# Display-Board_Rack-PDU_2_0.net
KiCad netlist of a schematic drawn in EAGLE
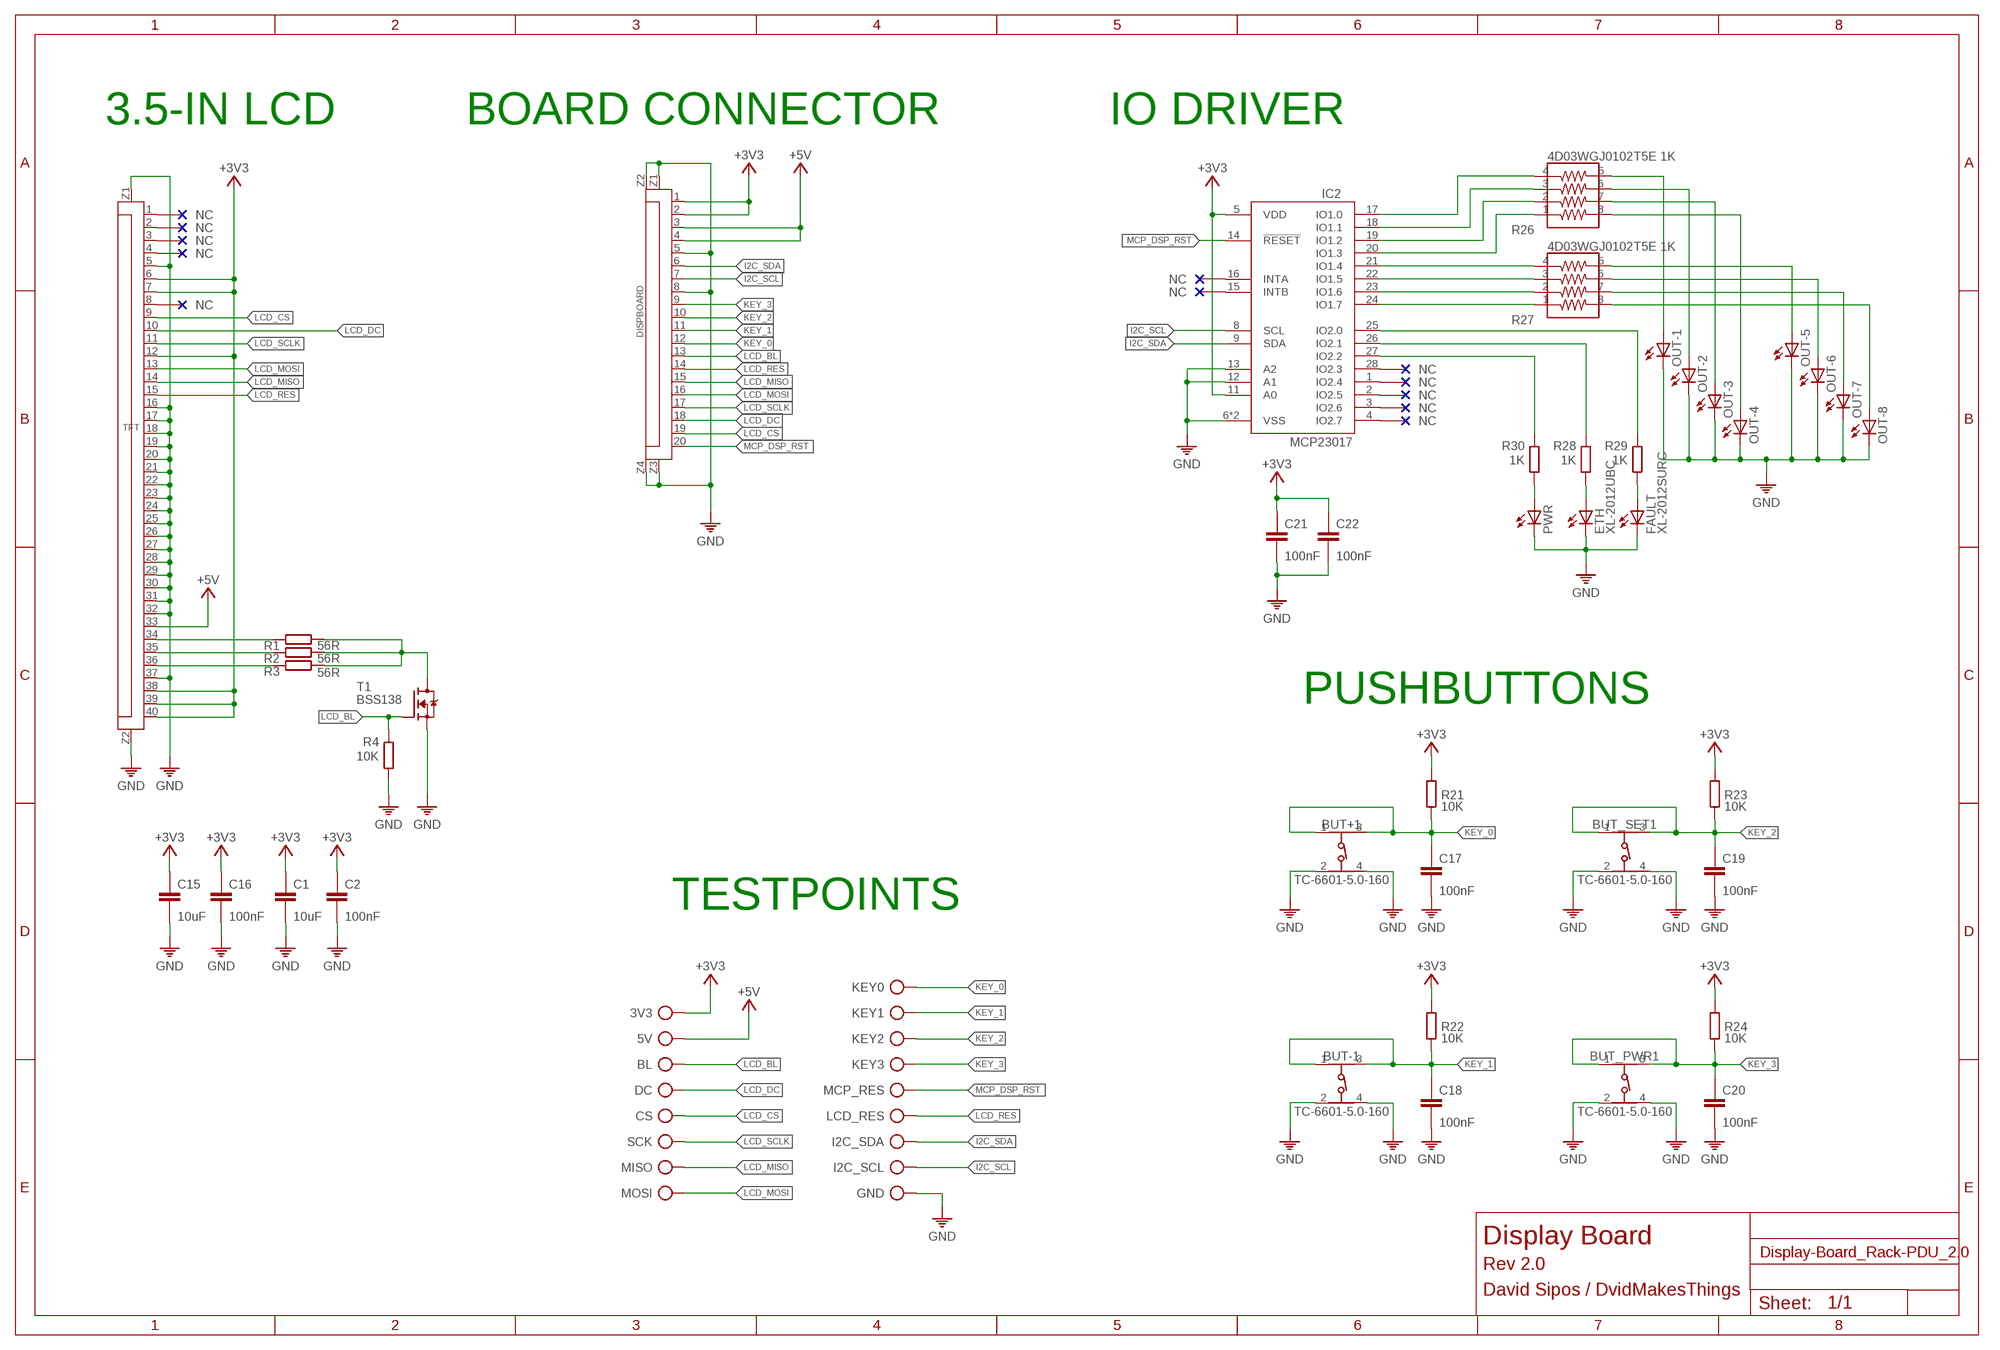
[diagram p0: schematic, sheet 1]

(export (version "E")
  (design (tool "Eeschema 10.0.6"))
  (components
    (comp (ref "3V3") (value "TP") (footprint "eagle-import:TP") (libsource (lib "eagle-import") (part "TP")))
    (comp (ref "5V") (value "TP") (footprint "eagle-import:TP") (libsource (lib "eagle-import") (part "TP")))
    (comp (ref "BL") (value "TP") (footprint "eagle-import:TP") (libsource (lib "eagle-import") (part "TP")))
    (comp (ref "BUT+1")
      (value "TC-6601-5.0-160")
      (footprint "eagle-import:430182043816")
      (libsource (lib "eagle-import") (part "430182043816"))
    )
    (comp (ref "BUT-1")
      (value "TC-6601-5.0-160")
      (footprint "eagle-import:430182043816")
      (libsource (lib "eagle-import") (part "430182043816"))
    )
    (comp (ref "BUT_PWR1")
      (value "TC-6601-5.0-160")
      (footprint "eagle-import:430182043816")
      (libsource (lib "eagle-import") (part "430182043816"))
    )
    (comp (ref "BUT_SET1")
      (value "TC-6601-5.0-160")
      (footprint "eagle-import:430182043816")
      (libsource (lib "eagle-import") (part "430182043816"))
    )
    (comp (ref "C1")
      (value "10uF")
      (footprint "eagle-import:C0402")
      (libsource (lib "eagle-import") (part "C-0402"))
    )
    (comp (ref "C2")
      (value "100nF")
      (footprint "eagle-import:C0402")
      (libsource (lib "eagle-import") (part "C-0402"))
    )
    (comp (ref "C15")
      (value "10uF")
      (footprint "eagle-import:C0402")
      (libsource (lib "eagle-import") (part "C-0402"))
    )
    (comp (ref "C16")
      (value "100nF")
      (footprint "eagle-import:C0402")
      (libsource (lib "eagle-import") (part "C-0402"))
    )
    (comp (ref "C17")
      (value "100nF")
      (footprint "eagle-import:C0402")
      (libsource (lib "eagle-import") (part "C-0402"))
    )
    (comp (ref "C18")
      (value "100nF")
      (footprint "eagle-import:C0402")
      (libsource (lib "eagle-import") (part "C-0402"))
    )
    (comp (ref "C19")
      (value "100nF")
      (footprint "eagle-import:C0402")
      (libsource (lib "eagle-import") (part "C-0402"))
    )
    (comp (ref "C20")
      (value "100nF")
      (footprint "eagle-import:C0402")
      (libsource (lib "eagle-import") (part "C-0402"))
    )
    (comp (ref "C21")
      (value "100nF")
      (footprint "eagle-import:C0402")
      (libsource (lib "eagle-import") (part "C-0402"))
    )
    (comp (ref "C22")
      (value "100nF")
      (footprint "eagle-import:C0402")
      (libsource (lib "eagle-import") (part "C-0402"))
    )
    (comp (ref "CS") (value "TP") (footprint "eagle-import:TP") (libsource (lib "eagle-import") (part "TP")))
    (comp (ref "DC") (value "TP") (footprint "eagle-import:TP") (libsource (lib "eagle-import") (part "TP")))
    (comp (ref "DISPBOARD")
      (value "FPC20-H")
      (footprint "eagle-import:FPC20")
      (libsource (lib "eagle-import") (part "FPC20-H"))
    )
    (comp (ref "ETH")
      (value "XL-2012UBC")
      (footprint "eagle-import:CHIP-LED0805")
      (libsource (lib "eagle-import") (part "LEDCHIP-LED0805"))
    )
    (comp (ref "FAULT")
      (value "XL-2012SURC")
      (footprint "eagle-import:CHIP-LED0805")
      (libsource (lib "eagle-import") (part "LEDCHIP-LED0805"))
    )
    (comp (ref "GND") (value "TP") (footprint "eagle-import:TP") (libsource (lib "eagle-import") (part "TP")))
    (comp (ref "I2C_SCL")
      (value "TP")
      (footprint "eagle-import:TP")
      (libsource (lib "eagle-import") (part "TP"))
    )
    (comp (ref "I2C_SDA")
      (value "TP")
      (footprint "eagle-import:TP")
      (libsource (lib "eagle-import") (part "TP"))
    )
    (comp (ref "IC2")
      (value "MCP23017-E/ML")
      (footprint "eagle-import:QFN28[6X6]ML")
      (libsource (lib "eagle-import") (part "MCP23017-E/ML"))
    )
    (comp (ref "KEY0")
      (value "TP")
      (footprint "eagle-import:TP")
      (libsource (lib "eagle-import") (part "TP"))
    )
    (comp (ref "KEY1")
      (value "TP")
      (footprint "eagle-import:TP")
      (libsource (lib "eagle-import") (part "TP"))
    )
    (comp (ref "KEY2")
      (value "TP")
      (footprint "eagle-import:TP")
      (libsource (lib "eagle-import") (part "TP"))
    )
    (comp (ref "KEY3")
      (value "TP")
      (footprint "eagle-import:TP")
      (libsource (lib "eagle-import") (part "TP"))
    )
    (comp (ref "LCD_RES")
      (value "TP")
      (footprint "eagle-import:TP")
      (libsource (lib "eagle-import") (part "TP"))
    )
    (comp (ref "MCP_RES")
      (value "TP")
      (footprint "eagle-import:TP")
      (libsource (lib "eagle-import") (part "TP"))
    )
    (comp (ref "MISO")
      (value "TP")
      (footprint "eagle-import:TP")
      (libsource (lib "eagle-import") (part "TP"))
    )
    (comp (ref "MOSI")
      (value "TP")
      (footprint "eagle-import:TP")
      (libsource (lib "eagle-import") (part "TP"))
    )
    (comp (ref "OUT-1")
      (value "LEDCHIP-LED0805")
      (footprint "eagle-import:CHIP-LED0805")
      (libsource (lib "eagle-import") (part "LEDCHIP-LED0805"))
    )
    (comp (ref "OUT-2")
      (value "LEDCHIP-LED0805")
      (footprint "eagle-import:CHIP-LED0805")
      (libsource (lib "eagle-import") (part "LEDCHIP-LED0805"))
    )
    (comp (ref "OUT-3")
      (value "LEDCHIP-LED0805")
      (footprint "eagle-import:CHIP-LED0805")
      (libsource (lib "eagle-import") (part "LEDCHIP-LED0805"))
    )
    (comp (ref "OUT-4")
      (value "LEDCHIP-LED0805")
      (footprint "eagle-import:CHIP-LED0805")
      (libsource (lib "eagle-import") (part "LEDCHIP-LED0805"))
    )
    (comp (ref "OUT-5")
      (value "LEDCHIP-LED0805")
      (footprint "eagle-import:CHIP-LED0805")
      (libsource (lib "eagle-import") (part "LEDCHIP-LED0805"))
    )
    (comp (ref "OUT-6")
      (value "LEDCHIP-LED0805")
      (footprint "eagle-import:CHIP-LED0805")
      (libsource (lib "eagle-import") (part "LEDCHIP-LED0805"))
    )
    (comp (ref "OUT-7")
      (value "LEDCHIP-LED0805")
      (footprint "eagle-import:CHIP-LED0805")
      (libsource (lib "eagle-import") (part "LEDCHIP-LED0805"))
    )
    (comp (ref "OUT-8")
      (value "LEDCHIP-LED0805")
      (footprint "eagle-import:CHIP-LED0805")
      (libsource (lib "eagle-import") (part "LEDCHIP-LED0805"))
    )
    (comp (ref "PWR")
      (value "LEDCHIP-LED0805")
      (footprint "eagle-import:CHIP-LED0805")
      (libsource (lib "eagle-import") (part "LEDCHIP-LED0805"))
    )
    (comp (ref "R1")
      (value "56R")
      (footprint "eagle-import:0402")
      (libsource (lib "eagle-import") (part "R0402"))
    )
    (comp (ref "R2")
      (value "56R")
      (footprint "eagle-import:0402")
      (libsource (lib "eagle-import") (part "R0402"))
    )
    (comp (ref "R3")
      (value "56R")
      (footprint "eagle-import:0402")
      (libsource (lib "eagle-import") (part "R0402"))
    )
    (comp (ref "R4")
      (value "10K")
      (footprint "eagle-import:0402")
      (libsource (lib "eagle-import") (part "R0402"))
    )
    (comp (ref "R21")
      (value "10K")
      (footprint "eagle-import:0402")
      (libsource (lib "eagle-import") (part "R0402"))
    )
    (comp (ref "R22")
      (value "10K")
      (footprint "eagle-import:0402")
      (libsource (lib "eagle-import") (part "R0402"))
    )
    (comp (ref "R23")
      (value "10K")
      (footprint "eagle-import:0402")
      (libsource (lib "eagle-import") (part "R0402"))
    )
    (comp (ref "R24")
      (value "10K")
      (footprint "eagle-import:0402")
      (libsource (lib "eagle-import") (part "R0402"))
    )
    (comp (ref "R26")
      (value "4D03WGJ0102T5E 1K")
      (footprint "eagle-import:742C083103JP")
      (fields
        (field (name "MANUFACTURER") "CTS Resistor Products")
        (field (name "MPN") "742C083103JP")
        (field (name "CREATED_BY") "PCBLayout.com")
      )
      (libsource (lib "eagle-import") (part "742C083103JP"))
    )
    (comp (ref "R27")
      (value "4D03WGJ0102T5E 1K")
      (footprint "eagle-import:742C083103JP")
      (fields
        (field (name "MANUFACTURER") "CTS Resistor Products")
        (field (name "MPN") "742C083103JP")
        (field (name "CREATED_BY") "PCBLayout.com")
      )
      (libsource (lib "eagle-import") (part "742C083103JP"))
    )
    (comp (ref "R28")
      (value "1K")
      (footprint "eagle-import:0402")
      (libsource (lib "eagle-import") (part "R0402"))
    )
    (comp (ref "R29")
      (value "1K")
      (footprint "eagle-import:0402")
      (libsource (lib "eagle-import") (part "R0402"))
    )
    (comp (ref "R30")
      (value "1K")
      (footprint "eagle-import:0402")
      (libsource (lib "eagle-import") (part "R0402"))
    )
    (comp (ref "SCK") (value "TP") (footprint "eagle-import:TP") (libsource (lib "eagle-import") (part "TP")))
    (comp (ref "T1")
      (value "BSS138")
      (footprint "eagle-import:SOT23")
      (libsource (lib "eagle-import") (part "BSS138"))
    )
    (comp (ref "TFT")
      (value "FPC40-HD")
      (footprint "eagle-import:FPC40_3.5TFT")
      (libsource (lib "eagle-import") (part "FPC40-HD"))
    )
  )
  (nets
    (net (code "1") (name "+3V3") (class "Default")
      (node (ref "3V3") (pin "TP") (pinfunction "P$1_TP") (pintype "bidirectional"))
      (node (ref "C1") (pin "1") (pinfunction "1_1") (pintype "passive"))
      (node (ref "C15") (pin "1") (pinfunction "1_1") (pintype "passive"))
      (node (ref "C16") (pin "1") (pinfunction "1_1") (pintype "passive"))
      (node (ref "C2") (pin "1") (pinfunction "1_1") (pintype "passive"))
      (node (ref "C21") (pin "1") (pinfunction "1_1") (pintype "passive"))
      (node (ref "C22") (pin "1") (pinfunction "1_1") (pintype "passive"))
      (node (ref "DISPBOARD") (pin "1") (pinfunction "1_1") (pintype "bidirectional"))
      (node (ref "DISPBOARD") (pin "2") (pinfunction "2_2") (pintype "bidirectional"))
      (node (ref "IC2") (pin "11") (pinfunction "A0_11") (pintype "bidirectional"))
      (node (ref "IC2") (pin "5") (pinfunction "VDD_5") (pintype "bidirectional"))
      (node (ref "R21") (pin "1") (pinfunction "1_1") (pintype "passive"))
      (node (ref "R22") (pin "1") (pinfunction "1_1") (pintype "passive"))
      (node (ref "R23") (pin "1") (pinfunction "1_1") (pintype "passive"))
      (node (ref "R24") (pin "1") (pinfunction "1_1") (pintype "passive"))
      (node (ref "TFT") (pin "12") (pinfunction "12_12") (pintype "bidirectional"))
      (node (ref "TFT") (pin "38") (pinfunction "38_38") (pintype "bidirectional"))
      (node (ref "TFT") (pin "39") (pinfunction "39_39") (pintype "bidirectional"))
      (node (ref "TFT") (pin "40") (pinfunction "40_40") (pintype "bidirectional"))
      (node (ref "TFT") (pin "6") (pinfunction "6_6") (pintype "bidirectional"))
      (node (ref "TFT") (pin "7") (pinfunction "7_7") (pintype "bidirectional"))
    )
    (net (code "2") (name "+5V") (class "Default")
      (node (ref "5V") (pin "TP") (pinfunction "P$1_TP") (pintype "bidirectional"))
      (node (ref "DISPBOARD") (pin "3") (pinfunction "3_3") (pintype "bidirectional"))
      (node (ref "DISPBOARD") (pin "4") (pinfunction "4_4") (pintype "bidirectional"))
      (node (ref "TFT") (pin "33") (pinfunction "33_33") (pintype "bidirectional"))
    )
    (net (code "3") (name "GND") (class "Default")
      (node (ref "BUT+1") (pin "2") (pinfunction "2_2") (pintype "passive"))
      (node (ref "BUT+1") (pin "4") (pinfunction "4_4") (pintype "passive"))
      (node (ref "BUT-1") (pin "2") (pinfunction "2_2") (pintype "passive"))
      (node (ref "BUT-1") (pin "4") (pinfunction "4_4") (pintype "passive"))
      (node (ref "BUT_PWR1") (pin "2") (pinfunction "2_2") (pintype "passive"))
      (node (ref "BUT_PWR1") (pin "4") (pinfunction "4_4") (pintype "passive"))
      (node (ref "BUT_SET1") (pin "2") (pinfunction "2_2") (pintype "passive"))
      (node (ref "BUT_SET1") (pin "4") (pinfunction "4_4") (pintype "passive"))
      (node (ref "C1") (pin "2") (pinfunction "2_2") (pintype "passive"))
      (node (ref "C15") (pin "2") (pinfunction "2_2") (pintype "passive"))
      (node (ref "C16") (pin "2") (pinfunction "2_2") (pintype "passive"))
      (node (ref "C17") (pin "2") (pinfunction "2_2") (pintype "passive"))
      (node (ref "C18") (pin "2") (pinfunction "2_2") (pintype "passive"))
      (node (ref "C19") (pin "2") (pinfunction "2_2") (pintype "passive"))
      (node (ref "C2") (pin "2") (pinfunction "2_2") (pintype "passive"))
      (node (ref "C20") (pin "2") (pinfunction "2_2") (pintype "passive"))
      (node (ref "C21") (pin "2") (pinfunction "2_2") (pintype "passive"))
      (node (ref "C22") (pin "2") (pinfunction "2_2") (pintype "passive"))
      (node (ref "DISPBOARD") (pin "5") (pinfunction "5_5") (pintype "bidirectional"))
      (node (ref "DISPBOARD") (pin "8") (pinfunction "8_8") (pintype "bidirectional"))
      (node (ref "DISPBOARD") (pin "Z1") (pinfunction "Z1_Z1") (pintype "bidirectional"))
      (node (ref "DISPBOARD") (pin "Z2") (pinfunction "Z2_Z2") (pintype "bidirectional"))
      (node (ref "DISPBOARD") (pin "Z3") (pinfunction "Z3_Z3") (pintype "bidirectional"))
      (node (ref "DISPBOARD") (pin "Z4") (pinfunction "Z4_Z4") (pintype "bidirectional"))
      (node (ref "ETH") (pin "C") (pinfunction "C_C") (pintype "passive"))
      (node (ref "FAULT") (pin "C") (pinfunction "C_C") (pintype "passive"))
      (node (ref "GND") (pin "TP") (pinfunction "P$1_TP") (pintype "bidirectional"))
      (node (ref "IC2") (pin "12") (pinfunction "A1_12") (pintype "bidirectional"))
      (node (ref "IC2") (pin "13") (pinfunction "A2_13") (pintype "bidirectional"))
      (node (ref "IC2") (pin "6") (pinfunction "VSS_6") (pintype "bidirectional"))
      (node (ref "IC2") (pin "PAD") (pinfunction "VSS_PAD") (pintype "bidirectional"))
      (node (ref "OUT-1") (pin "C") (pinfunction "C_C") (pintype "passive"))
      (node (ref "OUT-2") (pin "C") (pinfunction "C_C") (pintype "passive"))
      (node (ref "OUT-3") (pin "C") (pinfunction "C_C") (pintype "passive"))
      (node (ref "OUT-4") (pin "C") (pinfunction "C_C") (pintype "passive"))
      (node (ref "OUT-5") (pin "C") (pinfunction "C_C") (pintype "passive"))
      (node (ref "OUT-6") (pin "C") (pinfunction "C_C") (pintype "passive"))
      (node (ref "OUT-7") (pin "C") (pinfunction "C_C") (pintype "passive"))
      (node (ref "OUT-8") (pin "C") (pinfunction "C_C") (pintype "passive"))
      (node (ref "PWR") (pin "C") (pinfunction "C_C") (pintype "passive"))
      (node (ref "R4") (pin "2") (pinfunction "2_2") (pintype "passive"))
      (node (ref "T1") (pin "2") (pinfunction "S_2") (pintype "passive"))
      (node (ref "TFT") (pin "16") (pinfunction "16_16") (pintype "bidirectional"))
      (node (ref "TFT") (pin "17") (pinfunction "17_17") (pintype "bidirectional"))
      (node (ref "TFT") (pin "18") (pinfunction "18_18") (pintype "bidirectional"))
      (node (ref "TFT") (pin "19") (pinfunction "19_19") (pintype "bidirectional"))
      (node (ref "TFT") (pin "20") (pinfunction "20_20") (pintype "bidirectional"))
      (node (ref "TFT") (pin "21") (pinfunction "21_21") (pintype "bidirectional"))
      (node (ref "TFT") (pin "22") (pinfunction "22_22") (pintype "bidirectional"))
      (node (ref "TFT") (pin "23") (pinfunction "23_23") (pintype "bidirectional"))
      (node (ref "TFT") (pin "24") (pinfunction "24_24") (pintype "bidirectional"))
      (node (ref "TFT") (pin "25") (pinfunction "25_25") (pintype "bidirectional"))
      (node (ref "TFT") (pin "26") (pinfunction "26_26") (pintype "bidirectional"))
      (node (ref "TFT") (pin "27") (pinfunction "27_27") (pintype "bidirectional"))
      (node (ref "TFT") (pin "28") (pinfunction "28_28") (pintype "bidirectional"))
      (node (ref "TFT") (pin "29") (pinfunction "29_29") (pintype "bidirectional"))
      (node (ref "TFT") (pin "30") (pinfunction "30_30") (pintype "bidirectional"))
      (node (ref "TFT") (pin "31") (pinfunction "31_31") (pintype "bidirectional"))
      (node (ref "TFT") (pin "32") (pinfunction "32_32") (pintype "bidirectional"))
      (node (ref "TFT") (pin "37") (pinfunction "37_37") (pintype "bidirectional"))
      (node (ref "TFT") (pin "5") (pinfunction "5_5") (pintype "bidirectional"))
      (node (ref "TFT") (pin "Z1") (pinfunction "Z1_Z1") (pintype "bidirectional"))
      (node (ref "TFT") (pin "Z2") (pinfunction "Z2_Z2") (pintype "bidirectional"))
    )
    (net (code "4") (name "I2C_SCL") (class "Default")
      (node (ref "DISPBOARD") (pin "7") (pinfunction "7_7") (pintype "bidirectional"))
      (node (ref "I2C_SCL") (pin "TP") (pinfunction "P$1_TP") (pintype "bidirectional"))
      (node (ref "IC2") (pin "8") (pinfunction "SCL_8") (pintype "bidirectional"))
    )
    (net (code "5") (name "I2C_SDA") (class "Default")
      (node (ref "DISPBOARD") (pin "6") (pinfunction "6_6") (pintype "bidirectional"))
      (node (ref "I2C_SDA") (pin "TP") (pinfunction "P$1_TP") (pintype "bidirectional"))
      (node (ref "IC2") (pin "9") (pinfunction "SDA_9") (pintype "bidirectional"))
    )
    (net (code "6") (name "KEY_0") (class "Default")
      (node (ref "BUT+1") (pin "1") (pinfunction "1_1") (pintype "passive"))
      (node (ref "BUT+1") (pin "3") (pinfunction "3_3") (pintype "passive"))
      (node (ref "C17") (pin "1") (pinfunction "1_1") (pintype "passive"))
      (node (ref "DISPBOARD") (pin "12") (pinfunction "12_12") (pintype "bidirectional"))
      (node (ref "KEY0") (pin "TP") (pinfunction "P$1_TP") (pintype "bidirectional"))
      (node (ref "R21") (pin "2") (pinfunction "2_2") (pintype "passive"))
    )
    (net (code "7") (name "KEY_1") (class "Default")
      (node (ref "BUT-1") (pin "1") (pinfunction "1_1") (pintype "passive"))
      (node (ref "BUT-1") (pin "3") (pinfunction "3_3") (pintype "passive"))
      (node (ref "C18") (pin "1") (pinfunction "1_1") (pintype "passive"))
      (node (ref "DISPBOARD") (pin "11") (pinfunction "11_11") (pintype "bidirectional"))
      (node (ref "KEY1") (pin "TP") (pinfunction "P$1_TP") (pintype "bidirectional"))
      (node (ref "R22") (pin "2") (pinfunction "2_2") (pintype "passive"))
    )
    (net (code "8") (name "KEY_2") (class "Default")
      (node (ref "BUT_SET1") (pin "1") (pinfunction "1_1") (pintype "passive"))
      (node (ref "BUT_SET1") (pin "3") (pinfunction "3_3") (pintype "passive"))
      (node (ref "C19") (pin "1") (pinfunction "1_1") (pintype "passive"))
      (node (ref "DISPBOARD") (pin "10") (pinfunction "10_10") (pintype "bidirectional"))
      (node (ref "KEY2") (pin "TP") (pinfunction "P$1_TP") (pintype "bidirectional"))
      (node (ref "R23") (pin "2") (pinfunction "2_2") (pintype "passive"))
    )
    (net (code "9") (name "KEY_3") (class "Default")
      (node (ref "BUT_PWR1") (pin "1") (pinfunction "1_1") (pintype "passive"))
      (node (ref "BUT_PWR1") (pin "3") (pinfunction "3_3") (pintype "passive"))
      (node (ref "C20") (pin "1") (pinfunction "1_1") (pintype "passive"))
      (node (ref "DISPBOARD") (pin "9") (pinfunction "9_9") (pintype "bidirectional"))
      (node (ref "KEY3") (pin "TP") (pinfunction "P$1_TP") (pintype "bidirectional"))
      (node (ref "R24") (pin "2") (pinfunction "2_2") (pintype "passive"))
    )
    (net (code "10") (name "LCD_BL") (class "Default")
      (node (ref "BL") (pin "TP") (pinfunction "P$1_TP") (pintype "bidirectional"))
      (node (ref "DISPBOARD") (pin "13") (pinfunction "13_13") (pintype "bidirectional"))
      (node (ref "R4") (pin "1") (pinfunction "1_1") (pintype "passive"))
      (node (ref "T1") (pin "1") (pinfunction "G_1") (pintype "passive"))
    )
    (net (code "11") (name "LCD_CS") (class "Default")
      (node (ref "CS") (pin "TP") (pinfunction "P$1_TP") (pintype "bidirectional"))
      (node (ref "DISPBOARD") (pin "19") (pinfunction "19_19") (pintype "bidirectional"))
      (node (ref "TFT") (pin "9") (pinfunction "9_9") (pintype "bidirectional"))
    )
    (net (code "12") (name "LCD_DC") (class "Default")
      (node (ref "DC") (pin "TP") (pinfunction "P$1_TP") (pintype "bidirectional"))
      (node (ref "DISPBOARD") (pin "18") (pinfunction "18_18") (pintype "bidirectional"))
      (node (ref "TFT") (pin "10") (pinfunction "10_10") (pintype "bidirectional"))
    )
    (net (code "13") (name "LCD_MISO") (class "Default")
      (node (ref "DISPBOARD") (pin "15") (pinfunction "15_15") (pintype "bidirectional"))
      (node (ref "MISO") (pin "TP") (pinfunction "P$1_TP") (pintype "bidirectional"))
      (node (ref "TFT") (pin "14") (pinfunction "14_14") (pintype "bidirectional"))
    )
    (net (code "14") (name "LCD_MOSI") (class "Default")
      (node (ref "DISPBOARD") (pin "16") (pinfunction "16_16") (pintype "bidirectional"))
      (node (ref "MOSI") (pin "TP") (pinfunction "P$1_TP") (pintype "bidirectional"))
      (node (ref "TFT") (pin "13") (pinfunction "13_13") (pintype "bidirectional"))
    )
    (net (code "15") (name "LCD_RES") (class "Default")
      (node (ref "DISPBOARD") (pin "14") (pinfunction "14_14") (pintype "bidirectional"))
      (node (ref "LCD_RES") (pin "TP") (pinfunction "P$1_TP") (pintype "bidirectional"))
      (node (ref "TFT") (pin "15") (pinfunction "15_15") (pintype "bidirectional"))
    )
    (net (code "16") (name "LCD_SCLK") (class "Default")
      (node (ref "DISPBOARD") (pin "17") (pinfunction "17_17") (pintype "bidirectional"))
      (node (ref "SCK") (pin "TP") (pinfunction "P$1_TP") (pintype "bidirectional"))
      (node (ref "TFT") (pin "11") (pinfunction "11_11") (pintype "bidirectional"))
    )
    (net (code "17") (name "MCP_DSP_RST") (class "Default")
      (node (ref "DISPBOARD") (pin "20") (pinfunction "20_20") (pintype "bidirectional"))
      (node (ref "IC2") (pin "14") (pinfunction "~{RESET}_14") (pintype "bidirectional"))
      (node (ref "MCP_RES") (pin "TP") (pinfunction "P$1_TP") (pintype "bidirectional"))
    )
    (net (code "18") (name "Net-(ETH-PadA)") (class "Default")
      (node (ref "ETH") (pin "A") (pinfunction "A_A") (pintype "passive"))
      (node (ref "R28") (pin "2") (pinfunction "2_2") (pintype "passive"))
    )
    (net (code "19") (name "Net-(FAULT-PadA)") (class "Default")
      (node (ref "FAULT") (pin "A") (pinfunction "A_A") (pintype "passive"))
      (node (ref "R29") (pin "2") (pinfunction "2_2") (pintype "passive"))
    )
    (net (code "20") (name "Net-(IC2-IO1.0)") (class "Default")
      (node (ref "IC2") (pin "17") (pinfunction "IO1.0_17") (pintype "bidirectional"))
      (node (ref "R26") (pin "4") (pinfunction "4_4") (pintype "passive"))
    )
    (net (code "21") (name "Net-(IC2-IO1.1)") (class "Default")
      (node (ref "IC2") (pin "18") (pinfunction "IO1.1_18") (pintype "bidirectional"))
      (node (ref "R26") (pin "3") (pinfunction "3_3") (pintype "passive"))
    )
    (net (code "22") (name "Net-(IC2-IO1.2)") (class "Default")
      (node (ref "IC2") (pin "19") (pinfunction "IO1.2_19") (pintype "bidirectional"))
      (node (ref "R26") (pin "2") (pinfunction "2_2") (pintype "passive"))
    )
    (net (code "23") (name "Net-(IC2-IO1.3)") (class "Default")
      (node (ref "IC2") (pin "20") (pinfunction "IO1.3_20") (pintype "bidirectional"))
      (node (ref "R26") (pin "1") (pinfunction "1_1") (pintype "passive"))
    )
    (net (code "24") (name "Net-(IC2-IO1.4)") (class "Default")
      (node (ref "IC2") (pin "21") (pinfunction "IO1.4_21") (pintype "bidirectional"))
      (node (ref "R27") (pin "4") (pinfunction "4_4") (pintype "passive"))
    )
    (net (code "25") (name "Net-(IC2-IO1.5)") (class "Default")
      (node (ref "IC2") (pin "22") (pinfunction "IO1.5_22") (pintype "bidirectional"))
      (node (ref "R27") (pin "3") (pinfunction "3_3") (pintype "passive"))
    )
    (net (code "26") (name "Net-(IC2-IO1.6)") (class "Default")
      (node (ref "IC2") (pin "23") (pinfunction "IO1.6_23") (pintype "bidirectional"))
      (node (ref "R27") (pin "2") (pinfunction "2_2") (pintype "passive"))
    )
    (net (code "27") (name "Net-(IC2-IO1.7)") (class "Default")
      (node (ref "IC2") (pin "24") (pinfunction "IO1.7_24") (pintype "bidirectional"))
      (node (ref "R27") (pin "1") (pinfunction "1_1") (pintype "passive"))
    )
    (net (code "28") (name "Net-(IC2-IO2.0)") (class "Default")
      (node (ref "IC2") (pin "25") (pinfunction "IO2.0_25") (pintype "bidirectional"))
      (node (ref "R29") (pin "1") (pinfunction "1_1") (pintype "passive"))
    )
    (net (code "29") (name "Net-(IC2-IO2.1)") (class "Default")
      (node (ref "IC2") (pin "26") (pinfunction "IO2.1_26") (pintype "bidirectional"))
      (node (ref "R28") (pin "1") (pinfunction "1_1") (pintype "passive"))
    )
    (net (code "30") (name "Net-(IC2-IO2.2)") (class "Default")
      (node (ref "IC2") (pin "27") (pinfunction "IO2.2_27") (pintype "bidirectional"))
      (node (ref "R30") (pin "1") (pinfunction "1_1") (pintype "passive"))
    )
    (net (code "31") (name "Net-(OUT-1-PadA)") (class "Default")
      (node (ref "OUT-1") (pin "A") (pinfunction "A_A") (pintype "passive"))
      (node (ref "R26") (pin "5") (pinfunction "5_5") (pintype "passive"))
    )
    (net (code "32") (name "Net-(OUT-2-PadA)") (class "Default")
      (node (ref "OUT-2") (pin "A") (pinfunction "A_A") (pintype "passive"))
      (node (ref "R26") (pin "6") (pinfunction "6_6") (pintype "passive"))
    )
    (net (code "33") (name "Net-(OUT-3-PadA)") (class "Default")
      (node (ref "OUT-3") (pin "A") (pinfunction "A_A") (pintype "passive"))
      (node (ref "R26") (pin "7") (pinfunction "7_7") (pintype "passive"))
    )
    (net (code "34") (name "Net-(OUT-4-PadA)") (class "Default")
      (node (ref "OUT-4") (pin "A") (pinfunction "A_A") (pintype "passive"))
      (node (ref "R26") (pin "8") (pinfunction "8_8") (pintype "passive"))
    )
    (net (code "35") (name "Net-(OUT-5-PadA)") (class "Default")
      (node (ref "OUT-5") (pin "A") (pinfunction "A_A") (pintype "passive"))
      (node (ref "R27") (pin "5") (pinfunction "5_5") (pintype "passive"))
    )
    (net (code "36") (name "Net-(OUT-6-PadA)") (class "Default")
      (node (ref "OUT-6") (pin "A") (pinfunction "A_A") (pintype "passive"))
      (node (ref "R27") (pin "6") (pinfunction "6_6") (pintype "passive"))
    )
    (net (code "37") (name "Net-(OUT-7-PadA)") (class "Default")
      (node (ref "OUT-7") (pin "A") (pinfunction "A_A") (pintype "passive"))
      (node (ref "R27") (pin "7") (pinfunction "7_7") (pintype "passive"))
    )
    (net (code "38") (name "Net-(OUT-8-PadA)") (class "Default")
      (node (ref "OUT-8") (pin "A") (pinfunction "A_A") (pintype "passive"))
      (node (ref "R27") (pin "8") (pinfunction "8_8") (pintype "passive"))
    )
    (net (code "39") (name "Net-(PWR-PadA)") (class "Default")
      (node (ref "PWR") (pin "A") (pinfunction "A_A") (pintype "passive"))
      (node (ref "R30") (pin "2") (pinfunction "2_2") (pintype "passive"))
    )
    (net (code "40") (name "Net-(R1-Pad2)") (class "Default")
      (node (ref "R1") (pin "2") (pinfunction "2_2") (pintype "passive"))
      (node (ref "TFT") (pin "34") (pinfunction "34_34") (pintype "bidirectional"))
    )
    (net (code "41") (name "Net-(R2-Pad2)") (class "Default")
      (node (ref "R2") (pin "2") (pinfunction "2_2") (pintype "passive"))
      (node (ref "TFT") (pin "35") (pinfunction "35_35") (pintype "bidirectional"))
    )
    (net (code "42") (name "Net-(R3-Pad2)") (class "Default")
      (node (ref "R3") (pin "2") (pinfunction "2_2") (pintype "passive"))
      (node (ref "TFT") (pin "36") (pinfunction "36_36") (pintype "bidirectional"))
    )
    (net (code "43") (name "Net-(T1-D)") (class "Default")
      (node (ref "R1") (pin "1") (pinfunction "1_1") (pintype "passive"))
      (node (ref "R2") (pin "1") (pinfunction "1_1") (pintype "passive"))
      (node (ref "R3") (pin "1") (pinfunction "1_1") (pintype "passive"))
      (node (ref "T1") (pin "3") (pinfunction "D_3") (pintype "passive"))
    )
    (net (code "44") (name "unconnected-(IC2-INTA-Pad16)") (class "Default")
      (node (ref "IC2") (pin "16") (pinfunction "INTA_16") (pintype "bidirectional"))
    )
    (net (code "45") (name "unconnected-(IC2-INTB-Pad15)") (class "Default")
      (node (ref "IC2") (pin "15") (pinfunction "INTB_15") (pintype "bidirectional"))
    )
    (net (code "46") (name "unconnected-(IC2-IO2.3-Pad28)") (class "Default")
      (node (ref "IC2") (pin "28") (pinfunction "IO2.3_28") (pintype "bidirectional"))
    )
    (net (code "47") (name "unconnected-(IC2-IO2.4-Pad1)") (class "Default")
      (node (ref "IC2") (pin "1") (pinfunction "IO2.4_1") (pintype "bidirectional"))
    )
    (net (code "48") (name "unconnected-(IC2-IO2.5-Pad2)") (class "Default")
      (node (ref "IC2") (pin "2") (pinfunction "IO2.5_2") (pintype "bidirectional"))
    )
    (net (code "49") (name "unconnected-(IC2-IO2.6-Pad3)") (class "Default")
      (node (ref "IC2") (pin "3") (pinfunction "IO2.6_3") (pintype "bidirectional"))
    )
    (net (code "50") (name "unconnected-(IC2-IO2.7-Pad4)") (class "Default")
      (node (ref "IC2") (pin "4") (pinfunction "IO2.7_4") (pintype "bidirectional"))
    )
    (net (code "51") (name "unconnected-(TFT-Pad1)") (class "Default")
      (node (ref "TFT") (pin "1") (pinfunction "1_1") (pintype "bidirectional"))
    )
    (net (code "52") (name "unconnected-(TFT-Pad2)") (class "Default")
      (node (ref "TFT") (pin "2") (pinfunction "2_2") (pintype "bidirectional"))
    )
    (net (code "53") (name "unconnected-(TFT-Pad3)") (class "Default")
      (node (ref "TFT") (pin "3") (pinfunction "3_3") (pintype "bidirectional"))
    )
    (net (code "54") (name "unconnected-(TFT-Pad4)") (class "Default")
      (node (ref "TFT") (pin "4") (pinfunction "4_4") (pintype "bidirectional"))
    )
    (net (code "55") (name "unconnected-(TFT-Pad8)") (class "Default")
      (node (ref "TFT") (pin "8") (pinfunction "8_8") (pintype "bidirectional"))
    )
  )
)
